# ChromDot_Ring.net
KiCad netlist of a schematic drawn in EAGLE
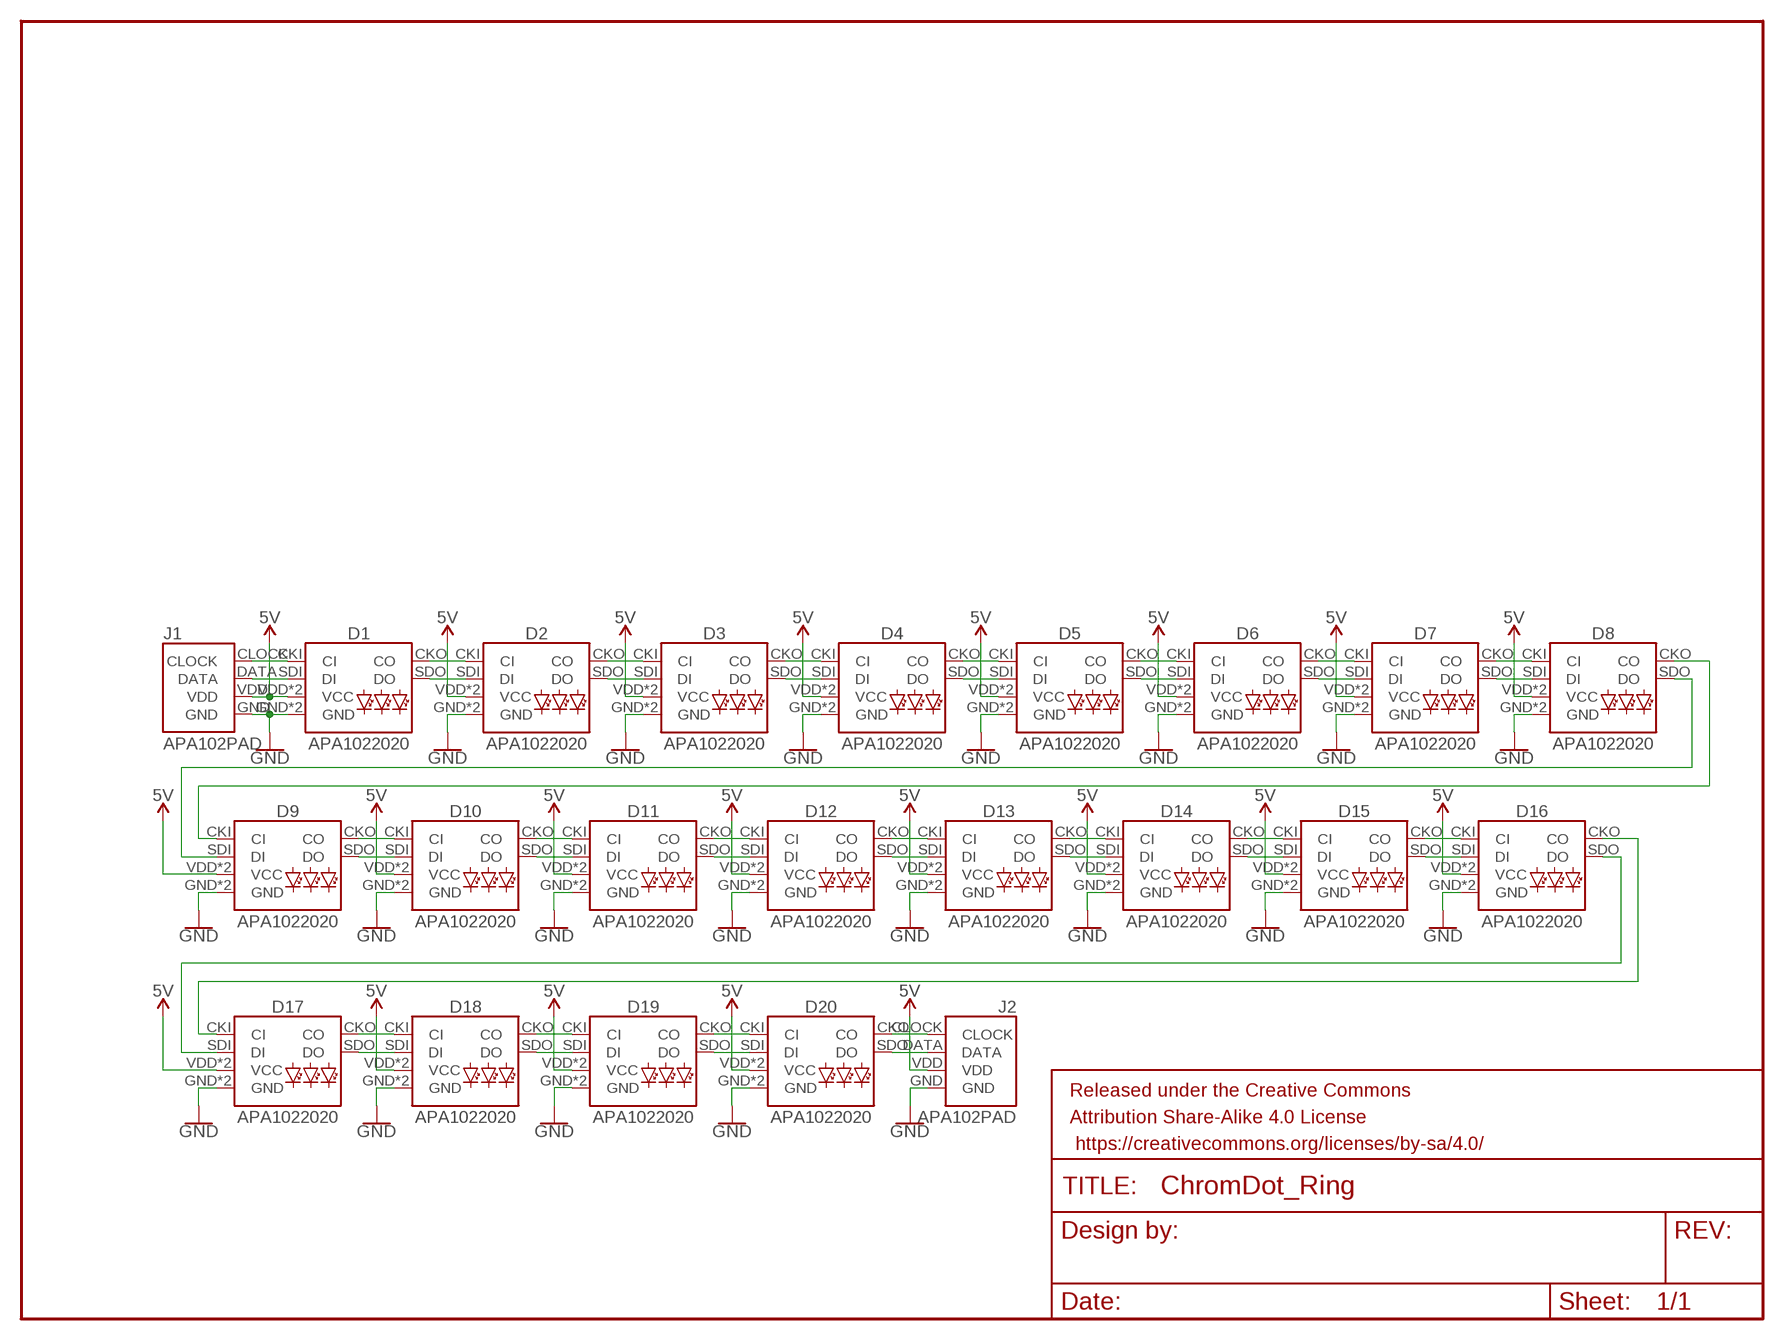
[diagram p0: schematic, sheet 1]

(export (version "E")
  (design (tool "Eeschema 10.0.6"))
  (components
    (comp (ref "D1")
      (value "APA1022020")
      (footprint "eagle-import:APA102-2020")
      (libsource (lib "eagle-import") (part "APA1022020"))
    )
    (comp (ref "D2")
      (value "APA1022020")
      (footprint "eagle-import:APA102-2020")
      (libsource (lib "eagle-import") (part "APA1022020"))
    )
    (comp (ref "D3")
      (value "APA1022020")
      (footprint "eagle-import:APA102-2020")
      (libsource (lib "eagle-import") (part "APA1022020"))
    )
    (comp (ref "D4")
      (value "APA1022020")
      (footprint "eagle-import:APA102-2020")
      (libsource (lib "eagle-import") (part "APA1022020"))
    )
    (comp (ref "D5")
      (value "APA1022020")
      (footprint "eagle-import:APA102-2020")
      (libsource (lib "eagle-import") (part "APA1022020"))
    )
    (comp (ref "D6")
      (value "APA1022020")
      (footprint "eagle-import:APA102-2020")
      (libsource (lib "eagle-import") (part "APA1022020"))
    )
    (comp (ref "D7")
      (value "APA1022020")
      (footprint "eagle-import:APA102-2020")
      (libsource (lib "eagle-import") (part "APA1022020"))
    )
    (comp (ref "D8")
      (value "APA1022020")
      (footprint "eagle-import:APA102-2020")
      (libsource (lib "eagle-import") (part "APA1022020"))
    )
    (comp (ref "D9")
      (value "APA1022020")
      (footprint "eagle-import:APA102-2020")
      (libsource (lib "eagle-import") (part "APA1022020"))
    )
    (comp (ref "D10")
      (value "APA1022020")
      (footprint "eagle-import:APA102-2020")
      (libsource (lib "eagle-import") (part "APA1022020"))
    )
    (comp (ref "D11")
      (value "APA1022020")
      (footprint "eagle-import:APA102-2020")
      (libsource (lib "eagle-import") (part "APA1022020"))
    )
    (comp (ref "D12")
      (value "APA1022020")
      (footprint "eagle-import:APA102-2020")
      (libsource (lib "eagle-import") (part "APA1022020"))
    )
    (comp (ref "D13")
      (value "APA1022020")
      (footprint "eagle-import:APA102-2020")
      (libsource (lib "eagle-import") (part "APA1022020"))
    )
    (comp (ref "D14")
      (value "APA1022020")
      (footprint "eagle-import:APA102-2020")
      (libsource (lib "eagle-import") (part "APA1022020"))
    )
    (comp (ref "D15")
      (value "APA1022020")
      (footprint "eagle-import:APA102-2020")
      (libsource (lib "eagle-import") (part "APA1022020"))
    )
    (comp (ref "D16")
      (value "APA1022020")
      (footprint "eagle-import:APA102-2020")
      (libsource (lib "eagle-import") (part "APA1022020"))
    )
    (comp (ref "D17")
      (value "APA1022020")
      (footprint "eagle-import:APA102-2020")
      (libsource (lib "eagle-import") (part "APA1022020"))
    )
    (comp (ref "D18")
      (value "APA1022020")
      (footprint "eagle-import:APA102-2020")
      (libsource (lib "eagle-import") (part "APA1022020"))
    )
    (comp (ref "D19")
      (value "APA1022020")
      (footprint "eagle-import:APA102-2020")
      (libsource (lib "eagle-import") (part "APA1022020"))
    )
    (comp (ref "D20")
      (value "APA1022020")
      (footprint "eagle-import:APA102-2020")
      (libsource (lib "eagle-import") (part "APA1022020"))
    )
    (comp (ref "FRAME1")
      (value "FRAME-LETTER")
      (footprint "eagle-import:CREATIVE_COMMONS")
      (libsource (lib "eagle-import") (part "FRAME-LETTER"))
    )
    (comp (ref "J1")
      (value "APA102PAD")
      (footprint "eagle-import:APA102PADS")
      (libsource (lib "eagle-import") (part "APA102PAD"))
    )
    (comp (ref "J2")
      (value "APA102PAD")
      (footprint "eagle-import:APA102PADS")
      (libsource (lib "eagle-import") (part "APA102PAD"))
    )
  )
  (nets
    (net (code "1") (name "5V") (class "Default")
      (node (ref "D1") (pin "VDD") (pinfunction "VCC_VDD") (pintype "bidirectional"))
      (node (ref "D1") (pin "VDDPAD") (pinfunction "VCC_VDDPAD") (pintype "bidirectional"))
      (node (ref "D10") (pin "VDD") (pinfunction "VCC_VDD") (pintype "bidirectional"))
      (node (ref "D10") (pin "VDDPAD") (pinfunction "VCC_VDDPAD") (pintype "bidirectional"))
      (node (ref "D11") (pin "VDD") (pinfunction "VCC_VDD") (pintype "bidirectional"))
      (node (ref "D11") (pin "VDDPAD") (pinfunction "VCC_VDDPAD") (pintype "bidirectional"))
      (node (ref "D12") (pin "VDD") (pinfunction "VCC_VDD") (pintype "bidirectional"))
      (node (ref "D12") (pin "VDDPAD") (pinfunction "VCC_VDDPAD") (pintype "bidirectional"))
      (node (ref "D13") (pin "VDD") (pinfunction "VCC_VDD") (pintype "bidirectional"))
      (node (ref "D13") (pin "VDDPAD") (pinfunction "VCC_VDDPAD") (pintype "bidirectional"))
      (node (ref "D14") (pin "VDD") (pinfunction "VCC_VDD") (pintype "bidirectional"))
      (node (ref "D14") (pin "VDDPAD") (pinfunction "VCC_VDDPAD") (pintype "bidirectional"))
      (node (ref "D15") (pin "VDD") (pinfunction "VCC_VDD") (pintype "bidirectional"))
      (node (ref "D15") (pin "VDDPAD") (pinfunction "VCC_VDDPAD") (pintype "bidirectional"))
      (node (ref "D16") (pin "VDD") (pinfunction "VCC_VDD") (pintype "bidirectional"))
      (node (ref "D16") (pin "VDDPAD") (pinfunction "VCC_VDDPAD") (pintype "bidirectional"))
      (node (ref "D17") (pin "VDD") (pinfunction "VCC_VDD") (pintype "bidirectional"))
      (node (ref "D17") (pin "VDDPAD") (pinfunction "VCC_VDDPAD") (pintype "bidirectional"))
      (node (ref "D18") (pin "VDD") (pinfunction "VCC_VDD") (pintype "bidirectional"))
      (node (ref "D18") (pin "VDDPAD") (pinfunction "VCC_VDDPAD") (pintype "bidirectional"))
      (node (ref "D19") (pin "VDD") (pinfunction "VCC_VDD") (pintype "bidirectional"))
      (node (ref "D19") (pin "VDDPAD") (pinfunction "VCC_VDDPAD") (pintype "bidirectional"))
      (node (ref "D2") (pin "VDD") (pinfunction "VCC_VDD") (pintype "bidirectional"))
      (node (ref "D2") (pin "VDDPAD") (pinfunction "VCC_VDDPAD") (pintype "bidirectional"))
      (node (ref "D20") (pin "VDD") (pinfunction "VCC_VDD") (pintype "bidirectional"))
      (node (ref "D20") (pin "VDDPAD") (pinfunction "VCC_VDDPAD") (pintype "bidirectional"))
      (node (ref "D3") (pin "VDD") (pinfunction "VCC_VDD") (pintype "bidirectional"))
      (node (ref "D3") (pin "VDDPAD") (pinfunction "VCC_VDDPAD") (pintype "bidirectional"))
      (node (ref "D4") (pin "VDD") (pinfunction "VCC_VDD") (pintype "bidirectional"))
      (node (ref "D4") (pin "VDDPAD") (pinfunction "VCC_VDDPAD") (pintype "bidirectional"))
      (node (ref "D5") (pin "VDD") (pinfunction "VCC_VDD") (pintype "bidirectional"))
      (node (ref "D5") (pin "VDDPAD") (pinfunction "VCC_VDDPAD") (pintype "bidirectional"))
      (node (ref "D6") (pin "VDD") (pinfunction "VCC_VDD") (pintype "bidirectional"))
      (node (ref "D6") (pin "VDDPAD") (pinfunction "VCC_VDDPAD") (pintype "bidirectional"))
      (node (ref "D7") (pin "VDD") (pinfunction "VCC_VDD") (pintype "bidirectional"))
      (node (ref "D7") (pin "VDDPAD") (pinfunction "VCC_VDDPAD") (pintype "bidirectional"))
      (node (ref "D8") (pin "VDD") (pinfunction "VCC_VDD") (pintype "bidirectional"))
      (node (ref "D8") (pin "VDDPAD") (pinfunction "VCC_VDDPAD") (pintype "bidirectional"))
      (node (ref "D9") (pin "VDD") (pinfunction "VCC_VDD") (pintype "bidirectional"))
      (node (ref "D9") (pin "VDDPAD") (pinfunction "VCC_VDDPAD") (pintype "bidirectional"))
      (node (ref "J1") (pin "VDD") (pinfunction "VDD_VDD") (pintype "bidirectional"))
      (node (ref "J2") (pin "VDD") (pinfunction "VDD_VDD") (pintype "bidirectional"))
    )
    (net (code "2") (name "GND") (class "Default")
      (node (ref "D1") (pin "GND") (pinfunction "GND_GND") (pintype "bidirectional"))
      (node (ref "D1") (pin "GNDPAD") (pinfunction "GND_GNDPAD") (pintype "bidirectional"))
      (node (ref "D10") (pin "GND") (pinfunction "GND_GND") (pintype "bidirectional"))
      (node (ref "D10") (pin "GNDPAD") (pinfunction "GND_GNDPAD") (pintype "bidirectional"))
      (node (ref "D11") (pin "GND") (pinfunction "GND_GND") (pintype "bidirectional"))
      (node (ref "D11") (pin "GNDPAD") (pinfunction "GND_GNDPAD") (pintype "bidirectional"))
      (node (ref "D12") (pin "GND") (pinfunction "GND_GND") (pintype "bidirectional"))
      (node (ref "D12") (pin "GNDPAD") (pinfunction "GND_GNDPAD") (pintype "bidirectional"))
      (node (ref "D13") (pin "GND") (pinfunction "GND_GND") (pintype "bidirectional"))
      (node (ref "D13") (pin "GNDPAD") (pinfunction "GND_GNDPAD") (pintype "bidirectional"))
      (node (ref "D14") (pin "GND") (pinfunction "GND_GND") (pintype "bidirectional"))
      (node (ref "D14") (pin "GNDPAD") (pinfunction "GND_GNDPAD") (pintype "bidirectional"))
      (node (ref "D15") (pin "GND") (pinfunction "GND_GND") (pintype "bidirectional"))
      (node (ref "D15") (pin "GNDPAD") (pinfunction "GND_GNDPAD") (pintype "bidirectional"))
      (node (ref "D16") (pin "GND") (pinfunction "GND_GND") (pintype "bidirectional"))
      (node (ref "D16") (pin "GNDPAD") (pinfunction "GND_GNDPAD") (pintype "bidirectional"))
      (node (ref "D17") (pin "GND") (pinfunction "GND_GND") (pintype "bidirectional"))
      (node (ref "D17") (pin "GNDPAD") (pinfunction "GND_GNDPAD") (pintype "bidirectional"))
      (node (ref "D18") (pin "GND") (pinfunction "GND_GND") (pintype "bidirectional"))
      (node (ref "D18") (pin "GNDPAD") (pinfunction "GND_GNDPAD") (pintype "bidirectional"))
      (node (ref "D19") (pin "GND") (pinfunction "GND_GND") (pintype "bidirectional"))
      (node (ref "D19") (pin "GNDPAD") (pinfunction "GND_GNDPAD") (pintype "bidirectional"))
      (node (ref "D2") (pin "GND") (pinfunction "GND_GND") (pintype "bidirectional"))
      (node (ref "D2") (pin "GNDPAD") (pinfunction "GND_GNDPAD") (pintype "bidirectional"))
      (node (ref "D20") (pin "GND") (pinfunction "GND_GND") (pintype "bidirectional"))
      (node (ref "D20") (pin "GNDPAD") (pinfunction "GND_GNDPAD") (pintype "bidirectional"))
      (node (ref "D3") (pin "GND") (pinfunction "GND_GND") (pintype "bidirectional"))
      (node (ref "D3") (pin "GNDPAD") (pinfunction "GND_GNDPAD") (pintype "bidirectional"))
      (node (ref "D4") (pin "GND") (pinfunction "GND_GND") (pintype "bidirectional"))
      (node (ref "D4") (pin "GNDPAD") (pinfunction "GND_GNDPAD") (pintype "bidirectional"))
      (node (ref "D5") (pin "GND") (pinfunction "GND_GND") (pintype "bidirectional"))
      (node (ref "D5") (pin "GNDPAD") (pinfunction "GND_GNDPAD") (pintype "bidirectional"))
      (node (ref "D6") (pin "GND") (pinfunction "GND_GND") (pintype "bidirectional"))
      (node (ref "D6") (pin "GNDPAD") (pinfunction "GND_GNDPAD") (pintype "bidirectional"))
      (node (ref "D7") (pin "GND") (pinfunction "GND_GND") (pintype "bidirectional"))
      (node (ref "D7") (pin "GNDPAD") (pinfunction "GND_GNDPAD") (pintype "bidirectional"))
      (node (ref "D8") (pin "GND") (pinfunction "GND_GND") (pintype "bidirectional"))
      (node (ref "D8") (pin "GNDPAD") (pinfunction "GND_GNDPAD") (pintype "bidirectional"))
      (node (ref "D9") (pin "GND") (pinfunction "GND_GND") (pintype "bidirectional"))
      (node (ref "D9") (pin "GNDPAD") (pinfunction "GND_GNDPAD") (pintype "bidirectional"))
      (node (ref "J1") (pin "GND") (pinfunction "GND_GND") (pintype "bidirectional"))
      (node (ref "J2") (pin "GND") (pinfunction "GND_GND") (pintype "bidirectional"))
    )
    (net (code "3") (name "Net-(D1-CI)") (class "Default")
      (node (ref "D1") (pin "CKI") (pinfunction "CI_CKI") (pintype "bidirectional"))
      (node (ref "J1") (pin "CLOCK") (pinfunction "CLOCK_CLOCK") (pintype "bidirectional"))
    )
    (net (code "4") (name "Net-(D1-CO)") (class "Default")
      (node (ref "D1") (pin "CKO") (pinfunction "CO_CKO") (pintype "bidirectional"))
      (node (ref "D2") (pin "CKI") (pinfunction "CI_CKI") (pintype "bidirectional"))
    )
    (net (code "5") (name "Net-(D1-DI)") (class "Default")
      (node (ref "D1") (pin "SDI") (pinfunction "DI_SDI") (pintype "bidirectional"))
      (node (ref "J1") (pin "DATA") (pinfunction "DATA_DATA") (pintype "bidirectional"))
    )
    (net (code "6") (name "Net-(D1-DO)") (class "Default")
      (node (ref "D1") (pin "SDO") (pinfunction "DO_SDO") (pintype "bidirectional"))
      (node (ref "D2") (pin "SDI") (pinfunction "DI_SDI") (pintype "bidirectional"))
    )
    (net (code "7") (name "Net-(D2-CO)") (class "Default")
      (node (ref "D2") (pin "CKO") (pinfunction "CO_CKO") (pintype "bidirectional"))
      (node (ref "D3") (pin "CKI") (pinfunction "CI_CKI") (pintype "bidirectional"))
    )
    (net (code "8") (name "Net-(D2-DO)") (class "Default")
      (node (ref "D2") (pin "SDO") (pinfunction "DO_SDO") (pintype "bidirectional"))
      (node (ref "D3") (pin "SDI") (pinfunction "DI_SDI") (pintype "bidirectional"))
    )
    (net (code "9") (name "Net-(D3-CO)") (class "Default")
      (node (ref "D3") (pin "CKO") (pinfunction "CO_CKO") (pintype "bidirectional"))
      (node (ref "D4") (pin "CKI") (pinfunction "CI_CKI") (pintype "bidirectional"))
    )
    (net (code "10") (name "Net-(D3-DO)") (class "Default")
      (node (ref "D3") (pin "SDO") (pinfunction "DO_SDO") (pintype "bidirectional"))
      (node (ref "D4") (pin "SDI") (pinfunction "DI_SDI") (pintype "bidirectional"))
    )
    (net (code "11") (name "Net-(D4-CO)") (class "Default")
      (node (ref "D4") (pin "CKO") (pinfunction "CO_CKO") (pintype "bidirectional"))
      (node (ref "D5") (pin "CKI") (pinfunction "CI_CKI") (pintype "bidirectional"))
    )
    (net (code "12") (name "Net-(D4-DO)") (class "Default")
      (node (ref "D4") (pin "SDO") (pinfunction "DO_SDO") (pintype "bidirectional"))
      (node (ref "D5") (pin "SDI") (pinfunction "DI_SDI") (pintype "bidirectional"))
    )
    (net (code "13") (name "Net-(D5-CO)") (class "Default")
      (node (ref "D5") (pin "CKO") (pinfunction "CO_CKO") (pintype "bidirectional"))
      (node (ref "D6") (pin "CKI") (pinfunction "CI_CKI") (pintype "bidirectional"))
    )
    (net (code "14") (name "Net-(D5-DO)") (class "Default")
      (node (ref "D5") (pin "SDO") (pinfunction "DO_SDO") (pintype "bidirectional"))
      (node (ref "D6") (pin "SDI") (pinfunction "DI_SDI") (pintype "bidirectional"))
    )
    (net (code "15") (name "Net-(D6-CO)") (class "Default")
      (node (ref "D6") (pin "CKO") (pinfunction "CO_CKO") (pintype "bidirectional"))
      (node (ref "D7") (pin "CKI") (pinfunction "CI_CKI") (pintype "bidirectional"))
    )
    (net (code "16") (name "Net-(D6-DO)") (class "Default")
      (node (ref "D6") (pin "SDO") (pinfunction "DO_SDO") (pintype "bidirectional"))
      (node (ref "D7") (pin "SDI") (pinfunction "DI_SDI") (pintype "bidirectional"))
    )
    (net (code "17") (name "Net-(D7-CO)") (class "Default")
      (node (ref "D7") (pin "CKO") (pinfunction "CO_CKO") (pintype "bidirectional"))
      (node (ref "D8") (pin "CKI") (pinfunction "CI_CKI") (pintype "bidirectional"))
    )
    (net (code "18") (name "Net-(D7-DO)") (class "Default")
      (node (ref "D7") (pin "SDO") (pinfunction "DO_SDO") (pintype "bidirectional"))
      (node (ref "D8") (pin "SDI") (pinfunction "DI_SDI") (pintype "bidirectional"))
    )
    (net (code "19") (name "Net-(D8-CO)") (class "Default")
      (node (ref "D8") (pin "CKO") (pinfunction "CO_CKO") (pintype "bidirectional"))
      (node (ref "D9") (pin "CKI") (pinfunction "CI_CKI") (pintype "bidirectional"))
    )
    (net (code "20") (name "Net-(D8-DO)") (class "Default")
      (node (ref "D8") (pin "SDO") (pinfunction "DO_SDO") (pintype "bidirectional"))
      (node (ref "D9") (pin "SDI") (pinfunction "DI_SDI") (pintype "bidirectional"))
    )
    (net (code "21") (name "Net-(D10-CI)") (class "Default")
      (node (ref "D10") (pin "CKI") (pinfunction "CI_CKI") (pintype "bidirectional"))
      (node (ref "D9") (pin "CKO") (pinfunction "CO_CKO") (pintype "bidirectional"))
    )
    (net (code "22") (name "Net-(D10-CO)") (class "Default")
      (node (ref "D10") (pin "CKO") (pinfunction "CO_CKO") (pintype "bidirectional"))
      (node (ref "D11") (pin "CKI") (pinfunction "CI_CKI") (pintype "bidirectional"))
    )
    (net (code "23") (name "Net-(D10-DI)") (class "Default")
      (node (ref "D10") (pin "SDI") (pinfunction "DI_SDI") (pintype "bidirectional"))
      (node (ref "D9") (pin "SDO") (pinfunction "DO_SDO") (pintype "bidirectional"))
    )
    (net (code "24") (name "Net-(D10-DO)") (class "Default")
      (node (ref "D10") (pin "SDO") (pinfunction "DO_SDO") (pintype "bidirectional"))
      (node (ref "D11") (pin "SDI") (pinfunction "DI_SDI") (pintype "bidirectional"))
    )
    (net (code "25") (name "Net-(D11-CO)") (class "Default")
      (node (ref "D11") (pin "CKO") (pinfunction "CO_CKO") (pintype "bidirectional"))
      (node (ref "D12") (pin "CKI") (pinfunction "CI_CKI") (pintype "bidirectional"))
    )
    (net (code "26") (name "Net-(D11-DO)") (class "Default")
      (node (ref "D11") (pin "SDO") (pinfunction "DO_SDO") (pintype "bidirectional"))
      (node (ref "D12") (pin "SDI") (pinfunction "DI_SDI") (pintype "bidirectional"))
    )
    (net (code "27") (name "Net-(D12-CO)") (class "Default")
      (node (ref "D12") (pin "CKO") (pinfunction "CO_CKO") (pintype "bidirectional"))
      (node (ref "D13") (pin "CKI") (pinfunction "CI_CKI") (pintype "bidirectional"))
    )
    (net (code "28") (name "Net-(D12-DO)") (class "Default")
      (node (ref "D12") (pin "SDO") (pinfunction "DO_SDO") (pintype "bidirectional"))
      (node (ref "D13") (pin "SDI") (pinfunction "DI_SDI") (pintype "bidirectional"))
    )
    (net (code "29") (name "Net-(D13-CO)") (class "Default")
      (node (ref "D13") (pin "CKO") (pinfunction "CO_CKO") (pintype "bidirectional"))
      (node (ref "D14") (pin "CKI") (pinfunction "CI_CKI") (pintype "bidirectional"))
    )
    (net (code "30") (name "Net-(D13-DO)") (class "Default")
      (node (ref "D13") (pin "SDO") (pinfunction "DO_SDO") (pintype "bidirectional"))
      (node (ref "D14") (pin "SDI") (pinfunction "DI_SDI") (pintype "bidirectional"))
    )
    (net (code "31") (name "Net-(D14-CO)") (class "Default")
      (node (ref "D14") (pin "CKO") (pinfunction "CO_CKO") (pintype "bidirectional"))
      (node (ref "D15") (pin "CKI") (pinfunction "CI_CKI") (pintype "bidirectional"))
    )
    (net (code "32") (name "Net-(D14-DO)") (class "Default")
      (node (ref "D14") (pin "SDO") (pinfunction "DO_SDO") (pintype "bidirectional"))
      (node (ref "D15") (pin "SDI") (pinfunction "DI_SDI") (pintype "bidirectional"))
    )
    (net (code "33") (name "Net-(D15-CO)") (class "Default")
      (node (ref "D15") (pin "CKO") (pinfunction "CO_CKO") (pintype "bidirectional"))
      (node (ref "D16") (pin "CKI") (pinfunction "CI_CKI") (pintype "bidirectional"))
    )
    (net (code "34") (name "Net-(D15-DO)") (class "Default")
      (node (ref "D15") (pin "SDO") (pinfunction "DO_SDO") (pintype "bidirectional"))
      (node (ref "D16") (pin "SDI") (pinfunction "DI_SDI") (pintype "bidirectional"))
    )
    (net (code "35") (name "Net-(D16-CO)") (class "Default")
      (node (ref "D16") (pin "CKO") (pinfunction "CO_CKO") (pintype "bidirectional"))
      (node (ref "D17") (pin "CKI") (pinfunction "CI_CKI") (pintype "bidirectional"))
    )
    (net (code "36") (name "Net-(D16-DO)") (class "Default")
      (node (ref "D16") (pin "SDO") (pinfunction "DO_SDO") (pintype "bidirectional"))
      (node (ref "D17") (pin "SDI") (pinfunction "DI_SDI") (pintype "bidirectional"))
    )
    (net (code "37") (name "Net-(D17-CO)") (class "Default")
      (node (ref "D17") (pin "CKO") (pinfunction "CO_CKO") (pintype "bidirectional"))
      (node (ref "D18") (pin "CKI") (pinfunction "CI_CKI") (pintype "bidirectional"))
    )
    (net (code "38") (name "Net-(D17-DO)") (class "Default")
      (node (ref "D17") (pin "SDO") (pinfunction "DO_SDO") (pintype "bidirectional"))
      (node (ref "D18") (pin "SDI") (pinfunction "DI_SDI") (pintype "bidirectional"))
    )
    (net (code "39") (name "Net-(D18-CO)") (class "Default")
      (node (ref "D18") (pin "CKO") (pinfunction "CO_CKO") (pintype "bidirectional"))
      (node (ref "D19") (pin "CKI") (pinfunction "CI_CKI") (pintype "bidirectional"))
    )
    (net (code "40") (name "Net-(D18-DO)") (class "Default")
      (node (ref "D18") (pin "SDO") (pinfunction "DO_SDO") (pintype "bidirectional"))
      (node (ref "D19") (pin "SDI") (pinfunction "DI_SDI") (pintype "bidirectional"))
    )
    (net (code "41") (name "Net-(D19-CO)") (class "Default")
      (node (ref "D19") (pin "CKO") (pinfunction "CO_CKO") (pintype "bidirectional"))
      (node (ref "D20") (pin "CKI") (pinfunction "CI_CKI") (pintype "bidirectional"))
    )
    (net (code "42") (name "Net-(D19-DO)") (class "Default")
      (node (ref "D19") (pin "SDO") (pinfunction "DO_SDO") (pintype "bidirectional"))
      (node (ref "D20") (pin "SDI") (pinfunction "DI_SDI") (pintype "bidirectional"))
    )
    (net (code "43") (name "Net-(D20-CO)") (class "Default")
      (node (ref "D20") (pin "CKO") (pinfunction "CO_CKO") (pintype "bidirectional"))
      (node (ref "J2") (pin "CLOCK") (pinfunction "CLOCK_CLOCK") (pintype "bidirectional"))
    )
    (net (code "44") (name "Net-(D20-DO)") (class "Default")
      (node (ref "D20") (pin "SDO") (pinfunction "DO_SDO") (pintype "bidirectional"))
      (node (ref "J2") (pin "DATA") (pinfunction "DATA_DATA") (pintype "bidirectional"))
    )
  )
)
